# lightswitchx2_triac.net
KiCad netlist of a schematic drawn in EAGLE
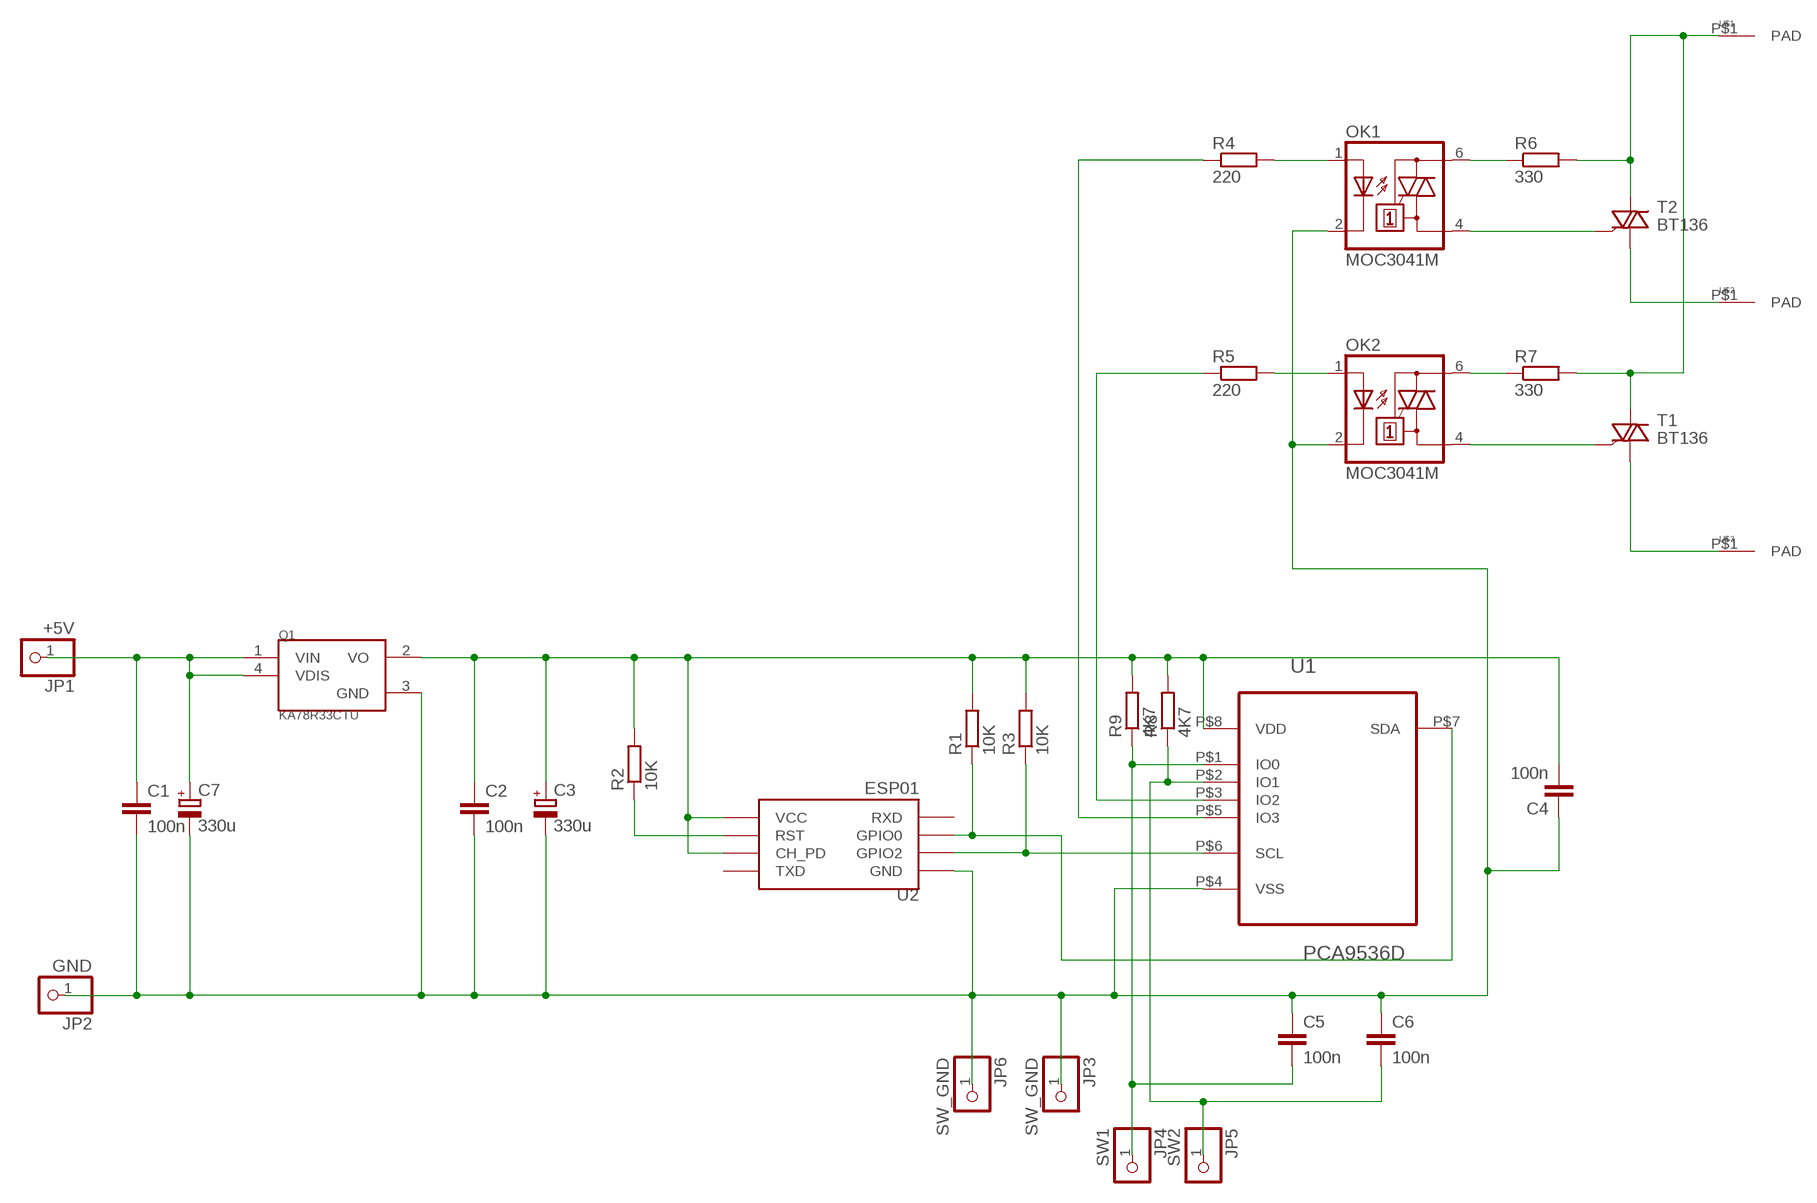
[diagram p0: schematic, sheet 1]

(export (version "E")
  (design (tool "Eeschema 10.0.6"))
  (components
    (comp (ref "C1")
      (value "100n")
      (footprint "eagle-import:C050-024X044")
      (libsource (lib "eagle-import") (part "C-EU050-024X044"))
    )
    (comp (ref "C2")
      (value "100n")
      (footprint "eagle-import:C050-024X044")
      (libsource (lib "eagle-import") (part "C-EU050-024X044"))
    )
    (comp (ref "C3")
      (value "330u")
      (footprint "eagle-import:E2-5")
      (libsource (lib "eagle-import") (part "CPOL-EUE2-5"))
    )
    (comp (ref "C4")
      (value "100n")
      (footprint "eagle-import:C050-024X044")
      (libsource (lib "eagle-import") (part "C-EU050-024X044"))
    )
    (comp (ref "C5")
      (value "100n")
      (footprint "eagle-import:C050-024X044")
      (libsource (lib "eagle-import") (part "C-EU050-024X044"))
    )
    (comp (ref "C6")
      (value "100n")
      (footprint "eagle-import:C050-024X044")
      (libsource (lib "eagle-import") (part "C-EU050-024X044"))
    )
    (comp (ref "C7")
      (value "330u")
      (footprint "eagle-import:E2-5")
      (libsource (lib "eagle-import") (part "CPOL-EUE2-5"))
    )
    (comp (ref "JP1")
      (value "+5V")
      (footprint "eagle-import:1X01")
      (libsource (lib "eagle-import") (part "PINHD-1X1"))
    )
    (comp (ref "JP2")
      (value "GND")
      (footprint "eagle-import:1X01")
      (libsource (lib "eagle-import") (part "PINHD-1X1"))
    )
    (comp (ref "JP3")
      (value "SW_GND")
      (footprint "eagle-import:1X01-CLEANBIG")
      (libsource (lib "eagle-import") (part "PINHD-1X1CB"))
    )
    (comp (ref "JP4")
      (value "SW1")
      (footprint "eagle-import:1X01-CLEANBIG")
      (libsource (lib "eagle-import") (part "PINHD-1X1CB"))
    )
    (comp (ref "JP5")
      (value "SW2")
      (footprint "eagle-import:1X01-CLEANBIG")
      (libsource (lib "eagle-import") (part "PINHD-1X1CB"))
    )
    (comp (ref "JP6")
      (value "SW_GND")
      (footprint "eagle-import:1X01-CLEANBIG")
      (libsource (lib "eagle-import") (part "PINHD-1X1CB"))
    )
    (comp (ref "OK1")
      (value "MOC3041M")
      (footprint "eagle-import:DIL06")
      (fields (field (name "MF") "FAIRCHILD SEMICONDUCTOR"))
      (libsource (lib "eagle-import") (part "MOC3041M"))
    )
    (comp (ref "OK2")
      (value "MOC3041M")
      (footprint "eagle-import:DIL06")
      (fields (field (name "MF") "FAIRCHILD SEMICONDUCTOR"))
      (libsource (lib "eagle-import") (part "MOC3041M"))
    )
    (comp (ref "Q1")
      (value "KA78R33CTU")
      (footprint "eagle-import:TO-220-4")
      (fields (field (name "MF") "Fairchild Semiconductor"))
      (libsource (lib "eagle-import") (part "KA78R33CTU"))
    )
    (comp (ref "R1")
      (value "10K")
      (footprint "eagle-import:0207_10")
      (libsource (lib "eagle-import") (part "R-EU_0207/10"))
    )
    (comp (ref "R2")
      (value "10K")
      (footprint "eagle-import:0204_7")
      (libsource (lib "eagle-import") (part "R-EU_0204/7"))
    )
    (comp (ref "R3")
      (value "10K")
      (footprint "eagle-import:0204_7")
      (libsource (lib "eagle-import") (part "R-EU_0204/7"))
    )
    (comp (ref "R4")
      (value "220")
      (footprint "eagle-import:0207_7")
      (libsource (lib "eagle-import") (part "R-EU_0207/7"))
    )
    (comp (ref "R5")
      (value "220")
      (footprint "eagle-import:0207_7")
      (libsource (lib "eagle-import") (part "R-EU_0207/7"))
    )
    (comp (ref "R6")
      (value "330")
      (footprint "eagle-import:0207_7")
      (libsource (lib "eagle-import") (part "R-EU_0207/7"))
    )
    (comp (ref "R7")
      (value "330")
      (footprint "eagle-import:0207_7")
      (libsource (lib "eagle-import") (part "R-EU_0207/7"))
    )
    (comp (ref "R8")
      (value "4K7")
      (footprint "eagle-import:0207_7")
      (libsource (lib "eagle-import") (part "R-EU_0207/7"))
    )
    (comp (ref "R9")
      (value "4K7")
      (footprint "eagle-import:0207_10")
      (libsource (lib "eagle-import") (part "R-EU_0207/10"))
    )
    (comp (ref "T1")
      (value "BT136")
      (footprint "eagle-import:TO220AB")
      (libsource (lib "eagle-import") (part "BT136"))
    )
    (comp (ref "T2")
      (value "BT136")
      (footprint "eagle-import:TO220AB")
      (libsource (lib "eagle-import") (part "BT136"))
    )
    (comp (ref "U$1")
      (value "PAD")
      (footprint "eagle-import:PAD")
      (libsource (lib "eagle-import") (part "PAD"))
    )
    (comp (ref "U$2")
      (value "PAD")
      (footprint "eagle-import:PAD")
      (libsource (lib "eagle-import") (part "PAD"))
    )
    (comp (ref "U$3")
      (value "PAD")
      (footprint "eagle-import:PAD")
      (libsource (lib "eagle-import") (part "PAD"))
    )
    (comp (ref "U1")
      (value "PCA9536D")
      (footprint "eagle-import:ADAPTER")
      (libsource (lib "eagle-import") (part "PCA9536D,118ADAPTER"))
    )
    (comp (ref "U2")
      (value "ESP01")
      (footprint "eagle-import:ESP01")
      (libsource (lib "eagle-import") (part "ESP01"))
    )
  )
  (nets
    (net (code "1") (name "Net-(OK1-A)") (class "Default")
      (node (ref "OK1") (pin "1") (pinfunction "A_1") (pintype "passive"))
      (node (ref "R4") (pin "2") (pinfunction "2_2") (pintype "passive"))
    )
    (net (code "2") (name "Net-(OK1-A1)") (class "Default")
      (node (ref "OK1") (pin "4") (pinfunction "A1_4") (pintype "passive"))
      (node (ref "T2") (pin "3") (pinfunction "G_3") (pintype "passive"))
    )
    (net (code "3") (name "Net-(OK1-A2)") (class "Default")
      (node (ref "OK1") (pin "6") (pinfunction "A2_6") (pintype "passive"))
      (node (ref "R6") (pin "1") (pinfunction "1_1") (pintype "passive"))
    )
    (net (code "4") (name "Net-(OK1-C)") (class "Default")
      (node (ref "C1") (pin "2") (pinfunction "2_2") (pintype "passive"))
      (node (ref "C2") (pin "2") (pinfunction "2_2") (pintype "passive"))
      (node (ref "C3") (pin "-") (pinfunction "-_-") (pintype "passive"))
      (node (ref "C4") (pin "1") (pinfunction "1_1") (pintype "passive"))
      (node (ref "C5") (pin "1") (pinfunction "1_1") (pintype "passive"))
      (node (ref "C6") (pin "1") (pinfunction "1_1") (pintype "passive"))
      (node (ref "C7") (pin "-") (pinfunction "-_-") (pintype "passive"))
      (node (ref "JP2") (pin "1") (pinfunction "1_1") (pintype "passive"))
      (node (ref "JP3") (pin "1") (pinfunction "1_1") (pintype "passive"))
      (node (ref "JP6") (pin "1") (pinfunction "1_1") (pintype "passive"))
      (node (ref "OK1") (pin "2") (pinfunction "C_2") (pintype "passive"))
      (node (ref "OK2") (pin "2") (pinfunction "C_2") (pintype "passive"))
      (node (ref "Q1") (pin "3") (pinfunction "GND_3") (pintype "passive"))
      (node (ref "U1") (pin "P$4") (pinfunction "VSS_P$4") (pintype "power_in"))
      (node (ref "U2") (pin "GND") (pinfunction "GND_GND") (pintype "bidirectional"))
    )
    (net (code "5") (name "Net-(OK2-A)") (class "Default")
      (node (ref "OK2") (pin "1") (pinfunction "A_1") (pintype "passive"))
      (node (ref "R5") (pin "2") (pinfunction "2_2") (pintype "passive"))
    )
    (net (code "6") (name "Net-(OK2-A1)") (class "Default")
      (node (ref "OK2") (pin "4") (pinfunction "A1_4") (pintype "passive"))
      (node (ref "T1") (pin "3") (pinfunction "G_3") (pintype "passive"))
    )
    (net (code "7") (name "Net-(OK2-A2)") (class "Default")
      (node (ref "OK2") (pin "6") (pinfunction "A2_6") (pintype "passive"))
      (node (ref "R7") (pin "1") (pinfunction "1_1") (pintype "passive"))
    )
    (net (code "8") (name "Net-(Q1-VDIS)") (class "Default")
      (node (ref "C1") (pin "1") (pinfunction "1_1") (pintype "passive"))
      (node (ref "C7") (pin "+") (pinfunction "+_+") (pintype "passive"))
      (node (ref "JP1") (pin "1") (pinfunction "1_1") (pintype "passive"))
      (node (ref "Q1") (pin "1") (pinfunction "VIN_1") (pintype "input"))
      (node (ref "Q1") (pin "4") (pinfunction "VDIS_4") (pintype "passive"))
    )
    (net (code "9") (name "Net-(Q1-VO)") (class "Default")
      (node (ref "C2") (pin "1") (pinfunction "1_1") (pintype "passive"))
      (node (ref "C3") (pin "+") (pinfunction "+_+") (pintype "passive"))
      (node (ref "C4") (pin "2") (pinfunction "2_2") (pintype "passive"))
      (node (ref "Q1") (pin "2") (pinfunction "VO_2") (pintype "output"))
      (node (ref "R1") (pin "2") (pinfunction "2_2") (pintype "passive"))
      (node (ref "R2") (pin "2") (pinfunction "2_2") (pintype "passive"))
      (node (ref "R3") (pin "2") (pinfunction "2_2") (pintype "passive"))
      (node (ref "R8") (pin "2") (pinfunction "2_2") (pintype "passive"))
      (node (ref "R9") (pin "2") (pinfunction "2_2") (pintype "passive"))
      (node (ref "U1") (pin "P$8") (pinfunction "VDD_P$8") (pintype "power_in"))
      (node (ref "U2") (pin "CH_PD") (pinfunction "CH_PD_CH_PD") (pintype "bidirectional"))
      (node (ref "U2") (pin "VCC") (pinfunction "VCC_VCC") (pintype "bidirectional"))
    )
    (net (code "10") (name "Net-(R2-Pad1)") (class "Default")
      (node (ref "R2") (pin "1") (pinfunction "1_1") (pintype "passive"))
      (node (ref "U2") (pin "RST") (pinfunction "RST_RST") (pintype "bidirectional"))
    )
    (net (code "11") (name "Net-(T1-A1)") (class "Default")
      (node (ref "T1") (pin "1") (pinfunction "A1_1") (pintype "passive"))
      (node (ref "U$3") (pin "P$1") (pinfunction "PAD_P$1") (pintype "bidirectional"))
    )
    (net (code "12") (name "Net-(T1-A2)") (class "Default")
      (node (ref "R6") (pin "2") (pinfunction "2_2") (pintype "passive"))
      (node (ref "R7") (pin "2") (pinfunction "2_2") (pintype "passive"))
      (node (ref "T1") (pin "2") (pinfunction "A2_2") (pintype "passive"))
      (node (ref "T2") (pin "2") (pinfunction "A2_2") (pintype "passive"))
      (node (ref "U$1") (pin "P$1") (pinfunction "PAD_P$1") (pintype "bidirectional"))
    )
    (net (code "13") (name "Net-(T2-A1)") (class "Default")
      (node (ref "T2") (pin "1") (pinfunction "A1_1") (pintype "passive"))
      (node (ref "U$2") (pin "P$1") (pinfunction "PAD_P$1") (pintype "bidirectional"))
    )
    (net (code "14") (name "Net-(U1-IO0)") (class "Default")
      (node (ref "C5") (pin "2") (pinfunction "2_2") (pintype "passive"))
      (node (ref "JP4") (pin "1") (pinfunction "1_1") (pintype "passive"))
      (node (ref "R9") (pin "1") (pinfunction "1_1") (pintype "passive"))
      (node (ref "U1") (pin "P$1") (pinfunction "IO0_P$1") (pintype "bidirectional"))
    )
    (net (code "15") (name "Net-(U1-IO1)") (class "Default")
      (node (ref "C6") (pin "2") (pinfunction "2_2") (pintype "passive"))
      (node (ref "JP5") (pin "1") (pinfunction "1_1") (pintype "passive"))
      (node (ref "R8") (pin "1") (pinfunction "1_1") (pintype "passive"))
      (node (ref "U1") (pin "P$2") (pinfunction "IO1_P$2") (pintype "bidirectional"))
    )
    (net (code "16") (name "Net-(U1-IO2)") (class "Default")
      (node (ref "R5") (pin "1") (pinfunction "1_1") (pintype "passive"))
      (node (ref "U1") (pin "P$3") (pinfunction "IO2_P$3") (pintype "bidirectional"))
    )
    (net (code "17") (name "Net-(U1-IO3)") (class "Default")
      (node (ref "R4") (pin "1") (pinfunction "1_1") (pintype "passive"))
      (node (ref "U1") (pin "P$5") (pinfunction "IO3_P$5") (pintype "bidirectional"))
    )
    (net (code "18") (name "Net-(U1-SCL)") (class "Default")
      (node (ref "R3") (pin "1") (pinfunction "1_1") (pintype "passive"))
      (node (ref "U1") (pin "P$6") (pinfunction "SCL_P$6") (pintype "input"))
      (node (ref "U2") (pin "GPIO2") (pinfunction "GPIO2_GPIO2") (pintype "bidirectional"))
    )
    (net (code "19") (name "Net-(U1-SDA)") (class "Default")
      (node (ref "R1") (pin "1") (pinfunction "1_1") (pintype "passive"))
      (node (ref "U1") (pin "P$7") (pinfunction "SDA_P$7") (pintype "bidirectional"))
      (node (ref "U2") (pin "GPIO0") (pinfunction "GPIO0_GPIO0") (pintype "bidirectional"))
    )
    (net (code "20") (name "unconnected-(U2-RXD-PadRX)") (class "Default")
      (node (ref "U2") (pin "RX") (pinfunction "RXD_RX") (pintype "bidirectional"))
    )
    (net (code "21") (name "unconnected-(U2-TXD-PadTX)") (class "Default")
      (node (ref "U2") (pin "TX") (pinfunction "TXD_TX") (pintype "bidirectional"))
    )
  )
)
